# micro8051.net
KiCad netlist of a schematic drawn in Altium Designer
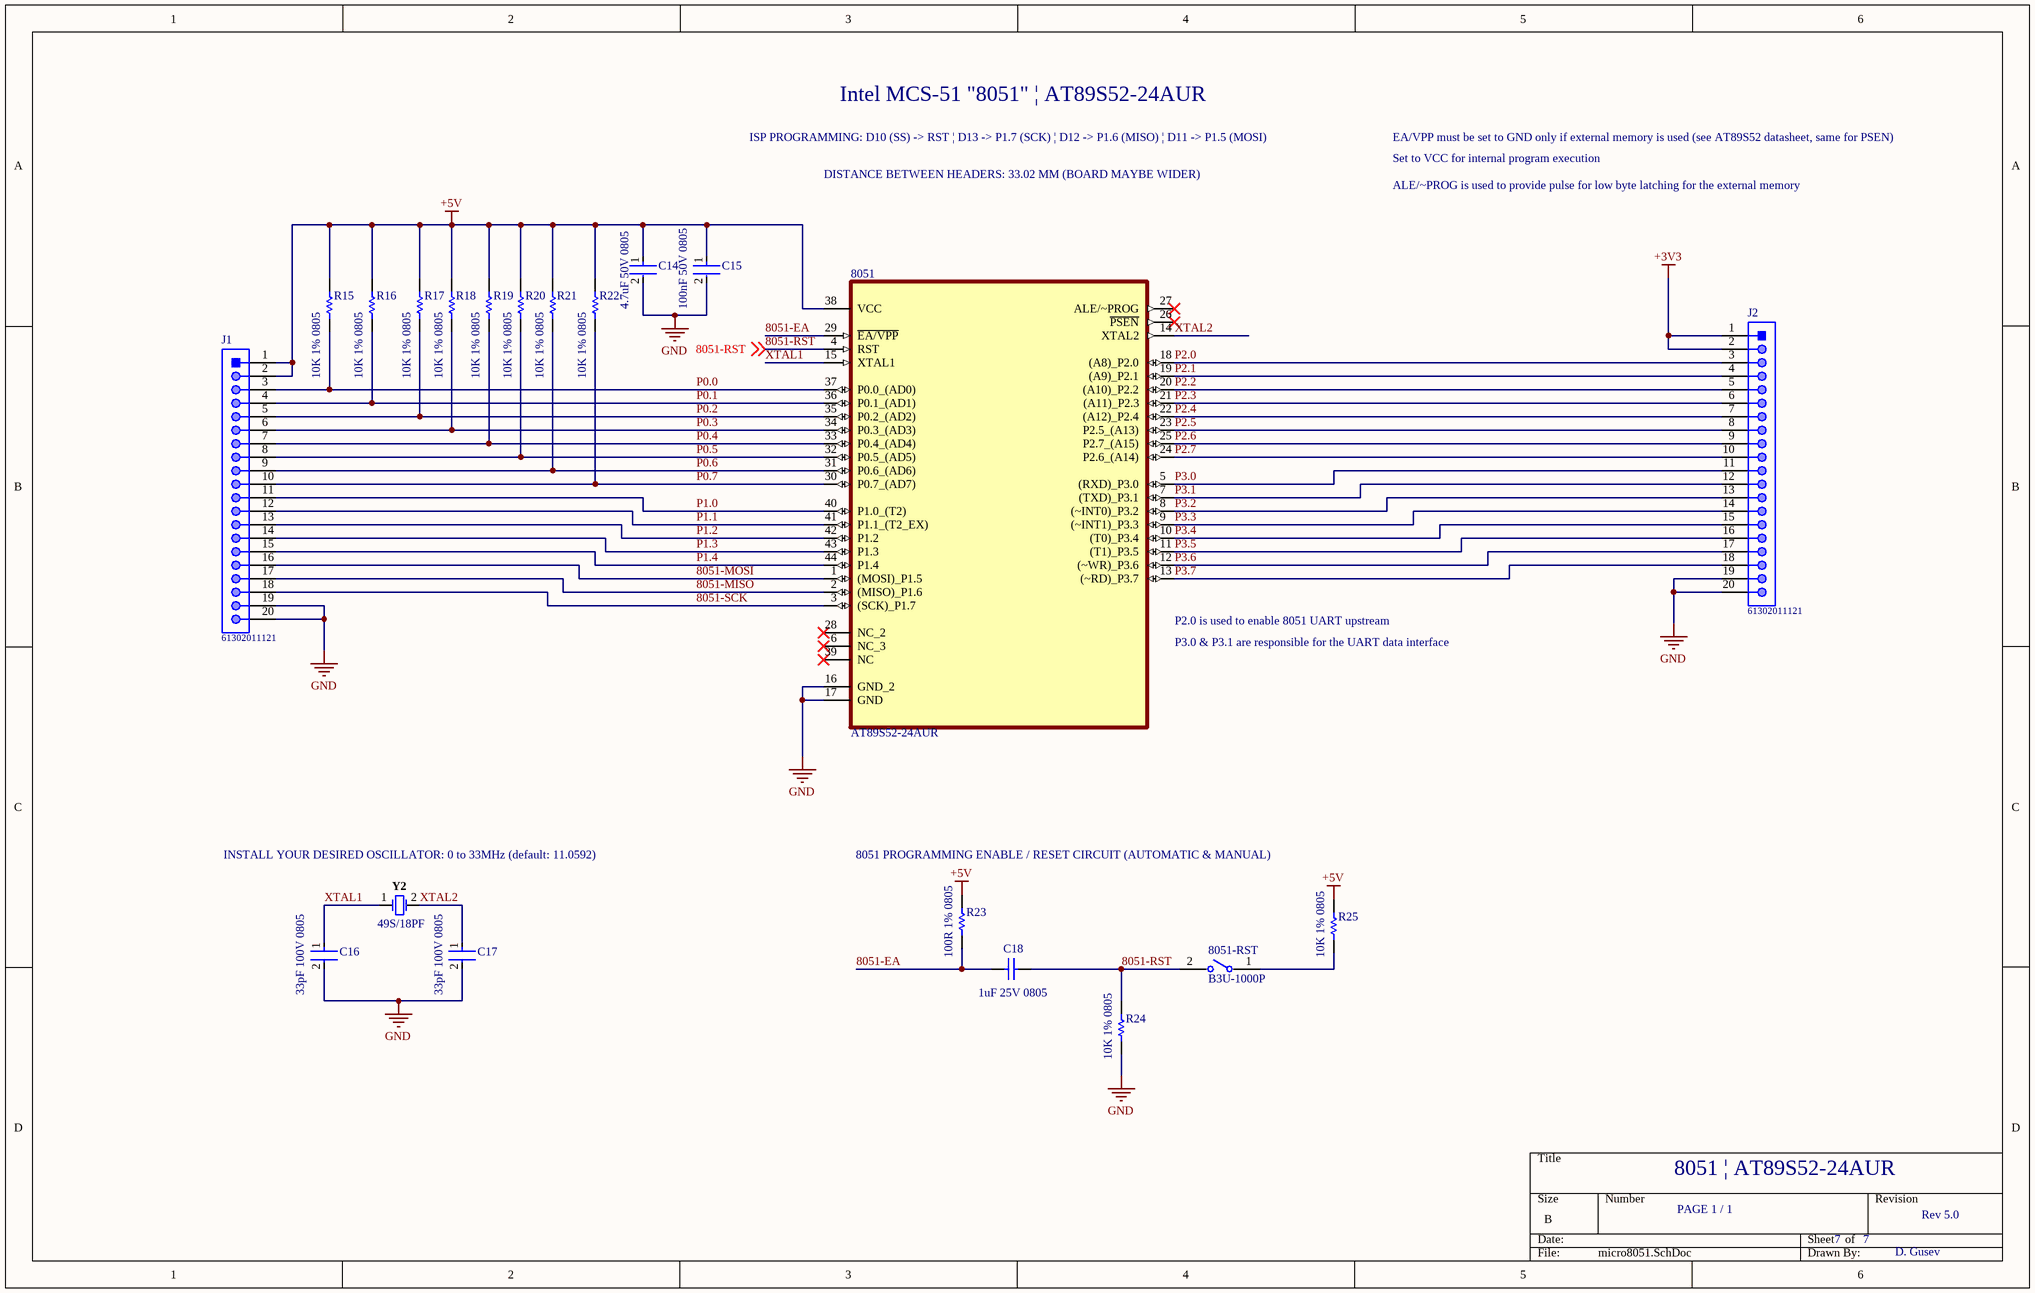
[diagram p0: micro8051.SchDoc]

(export (version "E")
  (design (tool "Eeschema 10.0.6"))
  (components
    (comp (ref "8051")
      (value "AT89S52-24AUR")
      (footprint "AT89S52-24AUR")
      (libsource (lib "micro8051") (part "AT89S52-24AUR"))
    )
    (comp (ref "8051-RST")
      (value "B3U-1000P")
      (footprint "FP-B3U-1000P-MFG")
      (description "SWITCH TACTILE SPST-NO 0.05A 12V")
      (libsource (lib "Altium Content Vault") (part "ae622034201233ca1abcedc05908f33"))
    )
    (comp (ref "C14")
      (value "4.7uF 50V 0805")
      (footprint "FP-C2012-125-MFG")
      (description "CAP CER 4.7UF 50V X5R 0805")
      (fields
        (field (name "TOLERANCE") "10%")
        (field (name "MANUFACTURER PART NUMBER") "C2012X5R1H475K125AB")
      )
      (libsource (lib "Altium Content Vault") (part "11868f565c42a9108669ba33697ecf6"))
    )
    (comp (ref "C15")
      (value "100nF 50V 0805")
      (footprint "FP-C0805C-DN-MFG")
      (description "CAP CER 0.1UF 50V X7R 0805")
      (fields
        (field (name "MANUFACTURER PART NUMBER") "C0805C104K5RACTU")
        (field (name "MANUFACTURER") "KEMET")
      )
      (libsource (lib "Altium Content Vault") (part "b4654b650e69147ec39a6b967a45e02"))
    )
    (comp (ref "C16")
      (value "33pF 100V 0805")
      (footprint "FP-C0805C-DN-MFG")
      (description "CAP CER 33PF 100V 5% NP0 0805")
      (fields (field (name "MANUFACTURER") "KEMET") (field (name "TOLERANCE") "0.05"))
      (libsource (lib "Altium Content Vault") (part "b4654b650e69147ec39a6b967a45e02"))
    )
    (comp (ref "C17")
      (value "33pF 100V 0805")
      (footprint "FP-C0805C-DN-MFG")
      (description "CAP CER 33PF 100V 5% NP0 0805")
      (fields (field (name "MANUFACTURER") "KEMET") (field (name "TOLERANCE") "0.05"))
      (libsource (lib "Altium Content Vault") (part "b4654b650e69147ec39a6b967a45e02"))
    )
    (comp (ref "C18")
      (value "1uF 25V 0805")
      (footprint "CAPC2013X140X50LL20T25")
      (fields (field (name "PART NUMBER") "C0805C105K3RACTU") (field (name "MANUFACTURER") "Kemet"))
      (libsource (lib "Altium Content Vault") (part "CAP"))
    )
    (comp (ref "J1")
      (value "61302011121")
      (footprint "61302011121")
      (description "THT Vertical Pin Header WR-PHD, Pitch 2.54 mm, Single Row, 20 pins")
      (fields (field (name "MANUFACTURER") "Wurth Elektronik") (field (name "PUBLISHER") "WurthElektronik"))
      (libsource (lib "Altium Content Vault") (part "WE-CN-1P-M-R20"))
    )
    (comp (ref "J2")
      (value "61302011121")
      (footprint "61302011121")
      (description "THT Vertical Pin Header WR-PHD, Pitch 2.54 mm, Single Row, 20 pins")
      (fields (field (name "MANUFACTURER") "Wurth Elektronik") (field (name "PUBLISHER") "WurthElektronik"))
      (libsource (lib "Altium Content Vault") (part "WE-CN-1P-M-R20"))
    )
    (comp (ref "R15")
      (value "10K 1% 0805")
      (footprint "RESC2013X60X35NL10T20")
      (description "Chip Resistor, 10 KOhm, +/- 1%, 0.125 W, -55 to 155 degC, 0805 (2012 Metric), RoHS, Tape and Reel")
      (fields (field (name "MANUFACTURER") "Yageo"))
      (libsource (lib "Altium Content Vault") (part "RES-2"))
    )
    (comp (ref "R16")
      (value "10K 1% 0805")
      (footprint "RESC2013X60X35NL10T20")
      (description "Chip Resistor, 10 KOhm, +/- 1%, 0.125 W, -55 to 155 degC, 0805 (2012 Metric), RoHS, Tape and Reel")
      (fields (field (name "MANUFACTURER") "Yageo"))
      (libsource (lib "Altium Content Vault") (part "RES-2"))
    )
    (comp (ref "R17")
      (value "10K 1% 0805")
      (footprint "RESC2013X60X35NL10T20")
      (description "Chip Resistor, 10 KOhm, +/- 1%, 0.125 W, -55 to 155 degC, 0805 (2012 Metric), RoHS, Tape and Reel")
      (fields (field (name "MANUFACTURER") "Yageo"))
      (libsource (lib "Altium Content Vault") (part "RES-2"))
    )
    (comp (ref "R18")
      (value "10K 1% 0805")
      (footprint "RESC2013X60X35NL10T20")
      (description "Chip Resistor, 10 KOhm, +/- 1%, 0.125 W, -55 to 155 degC, 0805 (2012 Metric), RoHS, Tape and Reel")
      (fields (field (name "MANUFACTURER") "Yageo"))
      (libsource (lib "Altium Content Vault") (part "RES-2"))
    )
    (comp (ref "R19")
      (value "10K 1% 0805")
      (footprint "RESC2013X60X35NL10T20")
      (description "Chip Resistor, 10 KOhm, +/- 1%, 0.125 W, -55 to 155 degC, 0805 (2012 Metric), RoHS, Tape and Reel")
      (fields (field (name "MANUFACTURER") "Yageo"))
      (libsource (lib "Altium Content Vault") (part "RES-2"))
    )
    (comp (ref "R20")
      (value "10K 1% 0805")
      (footprint "RESC2013X60X35NL10T20")
      (description "Chip Resistor, 10 KOhm, +/- 1%, 0.125 W, -55 to 155 degC, 0805 (2012 Metric), RoHS, Tape and Reel")
      (fields (field (name "MANUFACTURER") "Yageo"))
      (libsource (lib "Altium Content Vault") (part "RES-2"))
    )
    (comp (ref "R21")
      (value "10K 1% 0805")
      (footprint "RESC2013X60X35NL10T20")
      (description "Chip Resistor, 10 KOhm, +/- 1%, 0.125 W, -55 to 155 degC, 0805 (2012 Metric), RoHS, Tape and Reel")
      (fields (field (name "MANUFACTURER") "Yageo"))
      (libsource (lib "Altium Content Vault") (part "RES-2"))
    )
    (comp (ref "R22")
      (value "10K 1% 0805")
      (footprint "RESC2013X60X35NL10T20")
      (description "Chip Resistor, 10 KOhm, +/- 1%, 0.125 W, -55 to 155 degC, 0805 (2012 Metric), RoHS, Tape and Reel")
      (fields (field (name "MANUFACTURER") "Yageo"))
      (libsource (lib "Altium Content Vault") (part "RES-2"))
    )
    (comp (ref "R23")
      (value "100R 1% 0805")
      (footprint "RESC2013X60X35ML10T20")
      (description "Chip Resistor, 100 Ohm, +/-1%, 0.125 W, -55 to 155 degC, 0805 (2012 Metric), RoHS, Tape and Reel")
      (fields (field (name "TOLERANCE") "1%") (field (name "MANUFACTURER") "Yageo"))
      (libsource (lib "Altium Content Vault") (part "RES-2"))
    )
    (comp (ref "R24")
      (value "10K 1% 0805")
      (footprint "RESC2013X60X35NL10T20")
      (description "Chip Resistor, 10 KOhm, +/- 1%, 0.125 W, -55 to 155 degC, 0805 (2012 Metric), RoHS, Tape and Reel")
      (fields (field (name "MANUFACTURER") "Yageo"))
      (libsource (lib "Altium Content Vault") (part "RES-2"))
    )
    (comp (ref "R25")
      (value "10K 1% 0805")
      (footprint "RESC2013X60X35NL10T20")
      (description "Chip Resistor, 10 KOhm, +/- 1%, 0.125 W, -55 to 155 degC, 0805 (2012 Metric), RoHS, Tape and Reel")
      (fields (field (name "MANUFACTURER") "Yageo"))
      (libsource (lib "Altium Content Vault") (part "RES-2"))
    )
    (comp (ref "Y2")
      (value "49S/18PF")
      (footprint "JPY-49S-18PF")
      (description "Crystal, 16 MHz, 18 pF, -20 to 70 degC, 2-Pin THD")
      (fields (field (name "MANUFACTURER") "Shenzhen Jingpengyuan"))
      (libsource (lib "Altium Content Vault") (part "XTAL-1-2-2"))
    )
  )
  (nets
    (net (code "1") (name "+3V3") (class "Default")
      (node (ref "J2") (pin "1") (pinfunction "1_1") (pintype "passive"))
      (node (ref "J2") (pin "2") (pinfunction "2_2") (pintype "passive"))
    )
    (net (code "2") (name "+5V") (class "Default")
      (node (ref "8051") (pin "38") (pinfunction "VCC_38") (pintype "power_in"))
      (node (ref "C14") (pin "1") (pinfunction "1_1") (pintype "passive"))
      (node (ref "C15") (pin "1") (pinfunction "1_1") (pintype "passive"))
      (node (ref "J1") (pin "1") (pinfunction "1_1") (pintype "passive"))
      (node (ref "J1") (pin "2") (pinfunction "2_2") (pintype "passive"))
      (node (ref "R15") (pin "2") (pinfunction "2_2") (pintype "passive"))
      (node (ref "R16") (pin "2") (pinfunction "2_2") (pintype "passive"))
      (node (ref "R17") (pin "2") (pinfunction "2_2") (pintype "passive"))
      (node (ref "R18") (pin "2") (pinfunction "2_2") (pintype "passive"))
      (node (ref "R19") (pin "2") (pinfunction "2_2") (pintype "passive"))
      (node (ref "R20") (pin "2") (pinfunction "2_2") (pintype "passive"))
      (node (ref "R21") (pin "2") (pinfunction "2_2") (pintype "passive"))
      (node (ref "R22") (pin "2") (pinfunction "2_2") (pintype "passive"))
      (node (ref "R23") (pin "2") (pinfunction "2_2") (pintype "passive"))
      (node (ref "R25") (pin "2") (pinfunction "2_2") (pintype "passive"))
    )
    (net (code "3") (name "/8051-EA") (class "Default")
      (node (ref "8051") (pin "29") (pinfunction "~{EA/VPP}_29") (pintype "input"))
      (node (ref "C18") (pin "1") (pinfunction "1_1") (pintype "passive"))
      (node (ref "R23") (pin "1") (pinfunction "1_1") (pintype "passive"))
    )
    (net (code "4") (name "/8051-MISO") (class "Default")
      (node (ref "8051") (pin "2") (pinfunction "(MISO)_P1.6_2") (pintype "bidirectional"))
      (node (ref "J1") (pin "17") (pinfunction "17_17") (pintype "passive"))
    )
    (net (code "5") (name "/8051-MOSI") (class "Default")
      (node (ref "8051") (pin "1") (pinfunction "(MOSI)_P1.5_1") (pintype "bidirectional"))
      (node (ref "J1") (pin "16") (pinfunction "16_16") (pintype "passive"))
    )
    (net (code "6") (name "/8051-SCK") (class "Default")
      (node (ref "8051") (pin "3") (pinfunction "(SCK)_P1.7_3") (pintype "bidirectional"))
      (node (ref "J1") (pin "18") (pinfunction "18_18") (pintype "passive"))
    )
    (net (code "7") (name "/P0.0") (class "Default")
      (node (ref "8051") (pin "37") (pinfunction "P0.0_(AD0)_37") (pintype "bidirectional"))
      (node (ref "J1") (pin "3") (pinfunction "3_3") (pintype "passive"))
      (node (ref "R15") (pin "1") (pinfunction "1_1") (pintype "passive"))
    )
    (net (code "8") (name "/P0.1") (class "Default")
      (node (ref "8051") (pin "36") (pinfunction "P0.1_(AD1)_36") (pintype "bidirectional"))
      (node (ref "J1") (pin "4") (pinfunction "4_4") (pintype "passive"))
      (node (ref "R16") (pin "1") (pinfunction "1_1") (pintype "passive"))
    )
    (net (code "9") (name "/P0.2") (class "Default")
      (node (ref "8051") (pin "35") (pinfunction "P0.2_(AD2)_35") (pintype "bidirectional"))
      (node (ref "J1") (pin "5") (pinfunction "5_5") (pintype "passive"))
      (node (ref "R17") (pin "1") (pinfunction "1_1") (pintype "passive"))
    )
    (net (code "10") (name "/P0.3") (class "Default")
      (node (ref "8051") (pin "34") (pinfunction "P0.3_(AD3)_34") (pintype "bidirectional"))
      (node (ref "J1") (pin "6") (pinfunction "6_6") (pintype "passive"))
      (node (ref "R18") (pin "1") (pinfunction "1_1") (pintype "passive"))
    )
    (net (code "11") (name "/P0.4") (class "Default")
      (node (ref "8051") (pin "33") (pinfunction "P0.4_(AD4)_33") (pintype "bidirectional"))
      (node (ref "J1") (pin "7") (pinfunction "7_7") (pintype "passive"))
      (node (ref "R19") (pin "1") (pinfunction "1_1") (pintype "passive"))
    )
    (net (code "12") (name "/P0.5") (class "Default")
      (node (ref "8051") (pin "32") (pinfunction "P0.5_(AD5)_32") (pintype "bidirectional"))
      (node (ref "J1") (pin "8") (pinfunction "8_8") (pintype "passive"))
      (node (ref "R20") (pin "1") (pinfunction "1_1") (pintype "passive"))
    )
    (net (code "13") (name "/P0.6") (class "Default")
      (node (ref "8051") (pin "31") (pinfunction "P0.6_(AD6)_31") (pintype "bidirectional"))
      (node (ref "J1") (pin "9") (pinfunction "9_9") (pintype "passive"))
      (node (ref "R21") (pin "1") (pinfunction "1_1") (pintype "passive"))
    )
    (net (code "14") (name "/P0.7") (class "Default")
      (node (ref "8051") (pin "30") (pinfunction "P0.7_(AD7)_30") (pintype "bidirectional"))
      (node (ref "J1") (pin "10") (pinfunction "10_10") (pintype "passive"))
      (node (ref "R22") (pin "1") (pinfunction "1_1") (pintype "passive"))
    )
    (net (code "15") (name "/P1.0") (class "Default")
      (node (ref "8051") (pin "40") (pinfunction "P1.0_(T2)_40") (pintype "bidirectional"))
      (node (ref "J1") (pin "11") (pinfunction "11_11") (pintype "passive"))
    )
    (net (code "16") (name "/P1.1") (class "Default")
      (node (ref "8051") (pin "41") (pinfunction "P1.1_(T2_EX)_41") (pintype "bidirectional"))
      (node (ref "J1") (pin "12") (pinfunction "12_12") (pintype "passive"))
    )
    (net (code "17") (name "/P1.2") (class "Default")
      (node (ref "8051") (pin "42") (pinfunction "P1.2_42") (pintype "bidirectional"))
      (node (ref "J1") (pin "13") (pinfunction "13_13") (pintype "passive"))
    )
    (net (code "18") (name "/P1.3") (class "Default")
      (node (ref "8051") (pin "43") (pinfunction "P1.3_43") (pintype "bidirectional"))
      (node (ref "J1") (pin "14") (pinfunction "14_14") (pintype "passive"))
    )
    (net (code "19") (name "/P1.4") (class "Default")
      (node (ref "8051") (pin "44") (pinfunction "P1.4_44") (pintype "bidirectional"))
      (node (ref "J1") (pin "15") (pinfunction "15_15") (pintype "passive"))
    )
    (net (code "20") (name "/P2.0") (class "Default")
      (node (ref "8051") (pin "18") (pinfunction "(A8)_P2.0_18") (pintype "bidirectional"))
      (node (ref "J2") (pin "3") (pinfunction "3_3") (pintype "passive"))
    )
    (net (code "21") (name "/P2.1") (class "Default")
      (node (ref "8051") (pin "19") (pinfunction "(A9)_P2.1_19") (pintype "bidirectional"))
      (node (ref "J2") (pin "4") (pinfunction "4_4") (pintype "passive"))
    )
    (net (code "22") (name "/P2.2") (class "Default")
      (node (ref "8051") (pin "20") (pinfunction "(A10)_P2.2_20") (pintype "bidirectional"))
      (node (ref "J2") (pin "5") (pinfunction "5_5") (pintype "passive"))
    )
    (net (code "23") (name "/P2.3") (class "Default")
      (node (ref "8051") (pin "21") (pinfunction "(A11)_P2.3_21") (pintype "bidirectional"))
      (node (ref "J2") (pin "6") (pinfunction "6_6") (pintype "passive"))
    )
    (net (code "24") (name "/P2.4") (class "Default")
      (node (ref "8051") (pin "22") (pinfunction "(A12)_P2.4_22") (pintype "bidirectional"))
      (node (ref "J2") (pin "7") (pinfunction "7_7") (pintype "passive"))
    )
    (net (code "25") (name "/P2.5") (class "Default")
      (node (ref "8051") (pin "23") (pinfunction "P2.5_(A13)_23") (pintype "bidirectional"))
      (node (ref "J2") (pin "8") (pinfunction "8_8") (pintype "passive"))
    )
    (net (code "26") (name "/P2.6") (class "Default")
      (node (ref "8051") (pin "25") (pinfunction "P2.7_(A15)_25") (pintype "bidirectional"))
      (node (ref "J2") (pin "9") (pinfunction "9_9") (pintype "passive"))
    )
    (net (code "27") (name "/P2.7") (class "Default")
      (node (ref "8051") (pin "24") (pinfunction "P2.6_(A14)_24") (pintype "bidirectional"))
      (node (ref "J2") (pin "10") (pinfunction "10_10") (pintype "passive"))
    )
    (net (code "28") (name "/P3.0") (class "Default")
      (node (ref "8051") (pin "5") (pinfunction "(RXD)_P3.0_5") (pintype "bidirectional"))
      (node (ref "J2") (pin "11") (pinfunction "11_11") (pintype "passive"))
    )
    (net (code "29") (name "/P3.1") (class "Default")
      (node (ref "8051") (pin "7") (pinfunction "(TXD)_P3.1_7") (pintype "bidirectional"))
      (node (ref "J2") (pin "12") (pinfunction "12_12") (pintype "passive"))
    )
    (net (code "30") (name "/P3.2") (class "Default")
      (node (ref "8051") (pin "8") (pinfunction "(~INT0)_P3.2_8") (pintype "bidirectional"))
      (node (ref "J2") (pin "13") (pinfunction "13_13") (pintype "passive"))
    )
    (net (code "31") (name "/P3.3") (class "Default")
      (node (ref "8051") (pin "9") (pinfunction "(~INT1)_P3.3_9") (pintype "bidirectional"))
      (node (ref "J2") (pin "14") (pinfunction "14_14") (pintype "passive"))
    )
    (net (code "32") (name "/P3.4") (class "Default")
      (node (ref "8051") (pin "10") (pinfunction "(T0)_P3.4_10") (pintype "bidirectional"))
      (node (ref "J2") (pin "15") (pinfunction "15_15") (pintype "passive"))
    )
    (net (code "33") (name "/P3.5") (class "Default")
      (node (ref "8051") (pin "11") (pinfunction "(T1)_P3.5_11") (pintype "bidirectional"))
      (node (ref "J2") (pin "16") (pinfunction "16_16") (pintype "passive"))
    )
    (net (code "34") (name "/P3.6") (class "Default")
      (node (ref "8051") (pin "12") (pinfunction "(~WR)_P3.6_12") (pintype "bidirectional"))
      (node (ref "J2") (pin "17") (pinfunction "17_17") (pintype "passive"))
    )
    (net (code "35") (name "/P3.7") (class "Default")
      (node (ref "8051") (pin "13") (pinfunction "(~RD)_P3.7_13") (pintype "bidirectional"))
      (node (ref "J2") (pin "18") (pinfunction "18_18") (pintype "passive"))
    )
    (net (code "36") (name "/XTAL1") (class "Default")
      (node (ref "8051") (pin "15") (pinfunction "XTAL1_15") (pintype "input"))
      (node (ref "C16") (pin "1") (pinfunction "1_1") (pintype "passive"))
      (node (ref "Y2") (pin "1") (pinfunction "1_1") (pintype "passive"))
    )
    (net (code "37") (name "/XTAL2") (class "Default")
      (node (ref "8051") (pin "14") (pinfunction "XTAL2_14") (pintype "output"))
      (node (ref "C17") (pin "1") (pinfunction "1_1") (pintype "passive"))
      (node (ref "Y2") (pin "2") (pinfunction "2_2") (pintype "passive"))
    )
    (net (code "38") (name "8051-RST") (class "Default")
      (node (ref "8051") (pin "4") (pinfunction "RST_4") (pintype "input"))
      (node (ref "8051-RST") (pin "2") (pinfunction "2_2") (pintype "passive"))
      (node (ref "C18") (pin "2") (pinfunction "2_2") (pintype "passive"))
      (node (ref "R24") (pin "2") (pinfunction "2_2") (pintype "passive"))
    )
    (net (code "39") (name "GND") (class "Default")
      (node (ref "8051") (pin "16") (pinfunction "GND_2_16") (pintype "passive"))
      (node (ref "8051") (pin "17") (pinfunction "GND_17") (pintype "passive"))
      (node (ref "C14") (pin "2") (pinfunction "2_2") (pintype "passive"))
      (node (ref "C15") (pin "2") (pinfunction "2_2") (pintype "passive"))
      (node (ref "C16") (pin "2") (pinfunction "2_2") (pintype "passive"))
      (node (ref "C17") (pin "2") (pinfunction "2_2") (pintype "passive"))
      (node (ref "J1") (pin "19") (pinfunction "19_19") (pintype "passive"))
      (node (ref "J1") (pin "20") (pinfunction "20_20") (pintype "passive"))
      (node (ref "J2") (pin "19") (pinfunction "19_19") (pintype "passive"))
      (node (ref "J2") (pin "20") (pinfunction "20_20") (pintype "passive"))
      (node (ref "R24") (pin "1") (pinfunction "1_1") (pintype "passive"))
    )
    (net (code "40") (name "Net-(8051-RST-Pad1)") (class "Default")
      (node (ref "8051-RST") (pin "1") (pinfunction "1_1") (pintype "passive"))
      (node (ref "R25") (pin "1") (pinfunction "1_1") (pintype "passive"))
    )
    (net (code "41") (name "unconnected-(8051-ALE{slash}~PROG-Pad27)") (class "Default")
      (node (ref "8051") (pin "27") (pinfunction "ALE/~PROG_27") (pintype "output+no_connect"))
    )
    (net (code "42") (name "unconnected-(8051-NC-Pad39)") (class "Default")
      (node (ref "8051") (pin "39") (pinfunction "NC_39") (pintype "passive+no_connect"))
    )
    (net (code "43") (name "unconnected-(8051-NC_2-Pad28)") (class "Default")
      (node (ref "8051") (pin "28") (pinfunction "NC_2_28") (pintype "passive+no_connect"))
    )
    (net (code "44") (name "unconnected-(8051-NC_3-Pad6)") (class "Default")
      (node (ref "8051") (pin "6") (pinfunction "NC_3_6") (pintype "passive+no_connect"))
    )
    (net (code "45") (name "unconnected-(8051-~{PSEN}-Pad26)") (class "Default")
      (node (ref "8051") (pin "26") (pinfunction "~{PSEN}_26") (pintype "output+no_connect"))
    )
  )
)
